# chromatron_v1_0.net
KiCad netlist of a schematic drawn in EAGLE
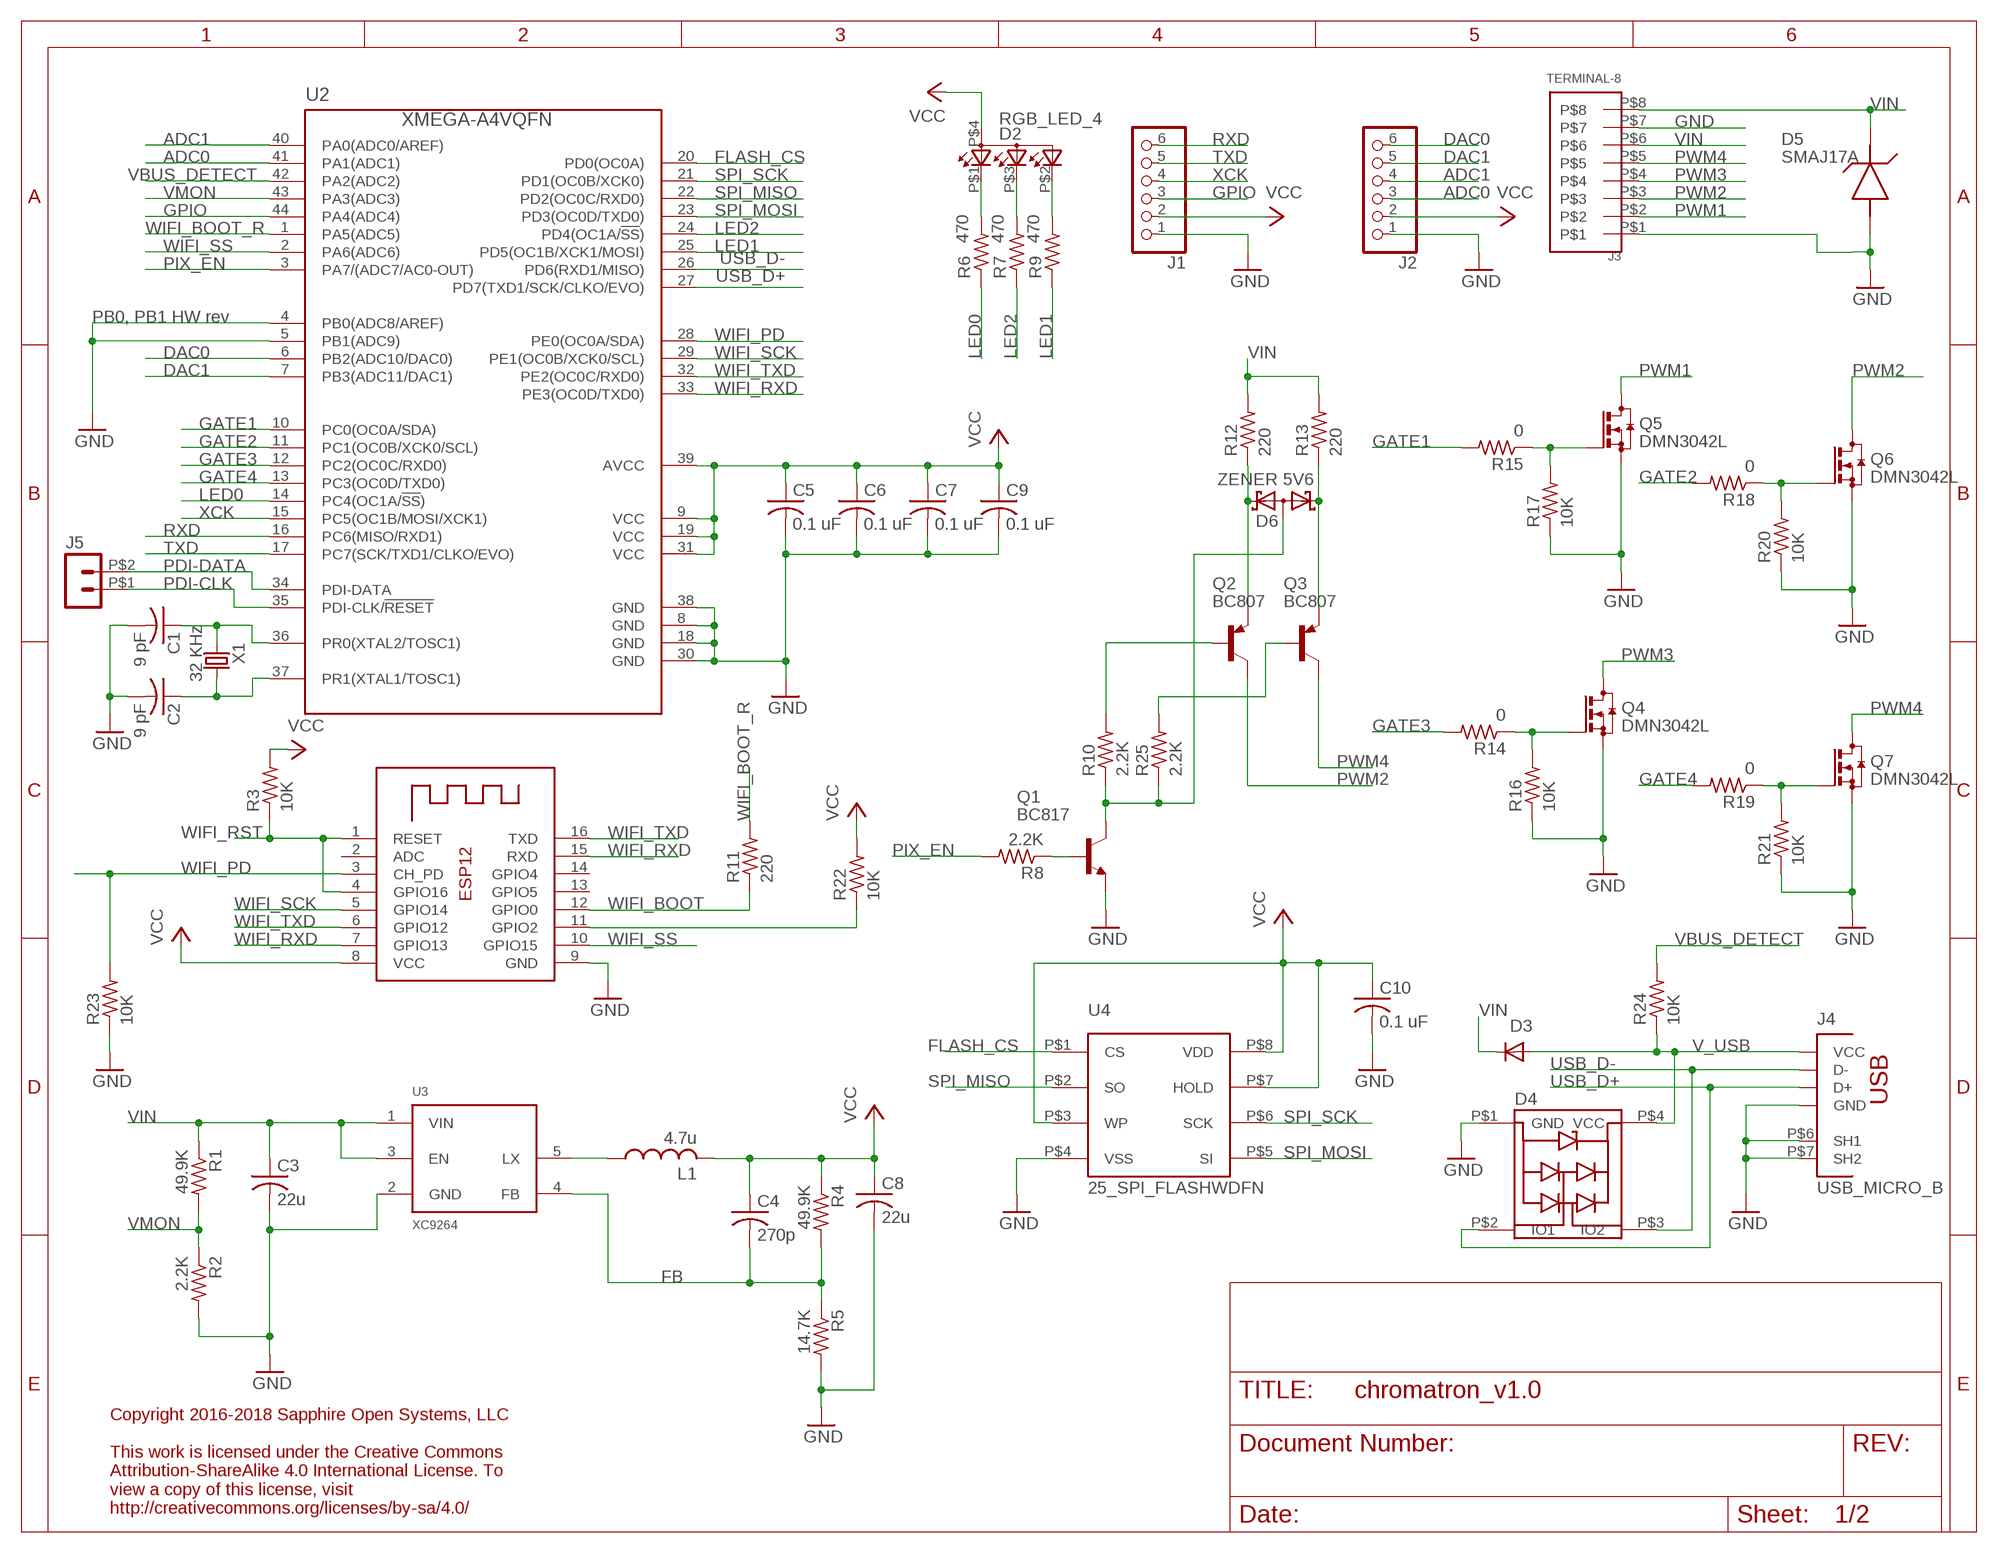
[diagram p0: schematic, sheet 1]
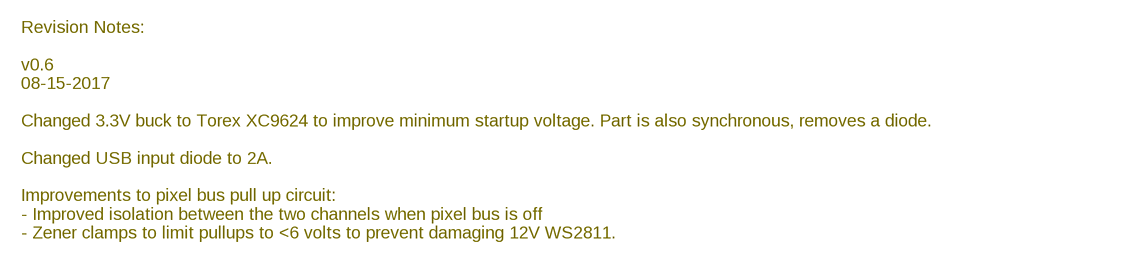
[diagram p1: schematic, sheet 2]

(export (version "E")
  (design (tool "Eeschema 10.0.6"))
  (components
    (comp (ref "C1")
      (value "9 pF")
      (footprint "eagle-import:C0402")
      (libsource (lib "eagle-import") (part "C-USC0402"))
    )
    (comp (ref "C2")
      (value "9 pF")
      (footprint "eagle-import:C0402")
      (libsource (lib "eagle-import") (part "C-USC0402"))
    )
    (comp (ref "C3")
      (value "22u")
      (footprint "eagle-import:C1206")
      (libsource (lib "eagle-import") (part "C-USC1206"))
    )
    (comp (ref "C4")
      (value "270p")
      (footprint "eagle-import:C0402")
      (libsource (lib "eagle-import") (part "C-USC0402"))
    )
    (comp (ref "C5")
      (value "0.1 uF")
      (footprint "eagle-import:C0402")
      (libsource (lib "eagle-import") (part "C-USC0402"))
    )
    (comp (ref "C6")
      (value "0.1 uF")
      (footprint "eagle-import:C0402")
      (libsource (lib "eagle-import") (part "C-USC0402"))
    )
    (comp (ref "C7")
      (value "0.1 uF")
      (footprint "eagle-import:C0402")
      (libsource (lib "eagle-import") (part "C-USC0402"))
    )
    (comp (ref "C8")
      (value "22u")
      (footprint "eagle-import:C1206")
      (libsource (lib "eagle-import") (part "C-USC1206"))
    )
    (comp (ref "C9")
      (value "0.1 uF")
      (footprint "eagle-import:C0402")
      (libsource (lib "eagle-import") (part "C-USC0402"))
    )
    (comp (ref "C10")
      (value "0.1 uF")
      (footprint "eagle-import:C0402")
      (libsource (lib "eagle-import") (part "C-USC0402"))
    )
    (comp (ref "D2")
      (value "RGB_LED_4")
      (footprint "eagle-import:0606-4")
      (libsource (lib "eagle-import") (part "RGB_LED_4"))
    )
    (comp (ref "D3")
      (value "2A")
      (footprint "eagle-import:SOD-123FL")
      (libsource (lib "eagle-import") (part "DIODE_SOD-123FL"))
    )
    (comp (ref "D4")
      (value "PTRTR5V0U2X")
      (footprint "eagle-import:SOT-143B")
      (libsource (lib "eagle-import") (part "PTRTR5V0U2X"))
    )
    (comp (ref "D5")
      (value "SMAJ17A")
      (footprint "eagle-import:SMA")
      (libsource (lib "eagle-import") (part "SMA_TVS"))
    )
    (comp (ref "D6")
      (value "ZENER 5V6")
      (footprint "eagle-import:SOT23")
      (libsource (lib "eagle-import") (part "BAT54A"))
    )
    (comp (ref "J1")
      (value "PINHD-1X6")
      (footprint "eagle-import:1X06")
      (libsource (lib "eagle-import") (part "PINHD-1X6"))
    )
    (comp (ref "J2")
      (value "PINHD-1X6")
      (footprint "eagle-import:1X06")
      (libsource (lib "eagle-import") (part "PINHD-1X6"))
    )
    (comp (ref "J3")
      (value "TERMINAL-8")
      (footprint "eagle-import:TERMINAL-8")
      (libsource (lib "eagle-import") (part "TERMINAL-8"))
    )
    (comp (ref "J4")
      (value "USB_MICRO_B")
      (footprint "eagle-import:USB-MICRO-B")
      (libsource (lib "eagle-import") (part "USB_MICRO_B"))
    )
    (comp (ref "J5")
      (value "PIN_HEADER_1X2")
      (footprint "eagle-import:PIN_HEADER_1X2")
      (libsource (lib "eagle-import") (part "PIN_HEADER_1X2"))
    )
    (comp (ref "L1")
      (value "4.7u")
      (footprint "eagle-import:L2012C")
      (libsource (lib "eagle-import") (part "L-USL2012C"))
    )
    (comp (ref "Q1")
      (value "BC817")
      (footprint "eagle-import:SOT23")
      (libsource (lib "eagle-import") (part "NPN"))
    )
    (comp (ref "Q2")
      (value "BC807")
      (footprint "eagle-import:SOT23")
      (libsource (lib "eagle-import") (part "PNP"))
    )
    (comp (ref "Q3")
      (value "BC807")
      (footprint "eagle-import:SOT23")
      (libsource (lib "eagle-import") (part "PNP"))
    )
    (comp (ref "Q4")
      (value "DMN3042L")
      (footprint "eagle-import:SOT23")
      (libsource (lib "eagle-import") (part "BSS123"))
    )
    (comp (ref "Q5")
      (value "DMN3042L")
      (footprint "eagle-import:SOT23")
      (libsource (lib "eagle-import") (part "BSS123"))
    )
    (comp (ref "Q6")
      (value "DMN3042L")
      (footprint "eagle-import:SOT23")
      (libsource (lib "eagle-import") (part "BSS123"))
    )
    (comp (ref "Q7")
      (value "DMN3042L")
      (footprint "eagle-import:SOT23")
      (libsource (lib "eagle-import") (part "BSS123"))
    )
    (comp (ref "R1")
      (value "49.9K")
      (footprint "eagle-import:R0402")
      (libsource (lib "eagle-import") (part "R-US_R0402"))
    )
    (comp (ref "R2")
      (value "2.2K")
      (footprint "eagle-import:R0402")
      (libsource (lib "eagle-import") (part "R-US_R0402"))
    )
    (comp (ref "R3")
      (value "10K")
      (footprint "eagle-import:R0402")
      (libsource (lib "eagle-import") (part "R-US_R0402"))
    )
    (comp (ref "R4")
      (value "49.9K")
      (footprint "eagle-import:R0402")
      (libsource (lib "eagle-import") (part "R-US_R0402"))
    )
    (comp (ref "R5")
      (value "14.7K")
      (footprint "eagle-import:R0402")
      (libsource (lib "eagle-import") (part "R-US_R0402"))
    )
    (comp (ref "R6")
      (value "470")
      (footprint "eagle-import:R0402")
      (libsource (lib "eagle-import") (part "R-US_R0402"))
    )
    (comp (ref "R7")
      (value "470")
      (footprint "eagle-import:R0402")
      (libsource (lib "eagle-import") (part "R-US_R0402"))
    )
    (comp (ref "R8")
      (value "2.2K")
      (footprint "eagle-import:R0402")
      (libsource (lib "eagle-import") (part "R-US_R0402"))
    )
    (comp (ref "R9")
      (value "470")
      (footprint "eagle-import:R0402")
      (libsource (lib "eagle-import") (part "R-US_R0402"))
    )
    (comp (ref "R10")
      (value "2.2K")
      (footprint "eagle-import:R0402")
      (libsource (lib "eagle-import") (part "R-US_R0402"))
    )
    (comp (ref "R11")
      (value "220")
      (footprint "eagle-import:R0402")
      (libsource (lib "eagle-import") (part "R-US_R0402"))
    )
    (comp (ref "R12")
      (value "220")
      (footprint "eagle-import:R0402")
      (libsource (lib "eagle-import") (part "R-US_R0402"))
    )
    (comp (ref "R13")
      (value "220")
      (footprint "eagle-import:R0402")
      (libsource (lib "eagle-import") (part "R-US_R0402"))
    )
    (comp (ref "R14")
      (value "0")
      (footprint "eagle-import:R0402")
      (libsource (lib "eagle-import") (part "R-US_R0402"))
    )
    (comp (ref "R15")
      (value "0")
      (footprint "eagle-import:R0402")
      (libsource (lib "eagle-import") (part "R-US_R0402"))
    )
    (comp (ref "R16")
      (value "10K")
      (footprint "eagle-import:R0402")
      (libsource (lib "eagle-import") (part "R-US_R0402"))
    )
    (comp (ref "R17")
      (value "10K")
      (footprint "eagle-import:R0402")
      (libsource (lib "eagle-import") (part "R-US_R0402"))
    )
    (comp (ref "R18")
      (value "0")
      (footprint "eagle-import:R0402")
      (libsource (lib "eagle-import") (part "R-US_R0402"))
    )
    (comp (ref "R19")
      (value "0")
      (footprint "eagle-import:R0402")
      (libsource (lib "eagle-import") (part "R-US_R0402"))
    )
    (comp (ref "R20")
      (value "10K")
      (footprint "eagle-import:R0402")
      (libsource (lib "eagle-import") (part "R-US_R0402"))
    )
    (comp (ref "R21")
      (value "10K")
      (footprint "eagle-import:R0402")
      (libsource (lib "eagle-import") (part "R-US_R0402"))
    )
    (comp (ref "R22")
      (value "10K")
      (footprint "eagle-import:R0402")
      (libsource (lib "eagle-import") (part "R-US_R0402"))
    )
    (comp (ref "R23")
      (value "10K")
      (footprint "eagle-import:R0402")
      (libsource (lib "eagle-import") (part "R-US_R0402"))
    )
    (comp (ref "R24")
      (value "10K")
      (footprint "eagle-import:R0402")
      (libsource (lib "eagle-import") (part "R-US_R0402"))
    )
    (comp (ref "R25")
      (value "2.2K")
      (footprint "eagle-import:R0402")
      (libsource (lib "eagle-import") (part "R-US_R0402"))
    )
    (comp (ref "U1")
      (value "ESP-12")
      (footprint "eagle-import:ESP-12")
      (libsource (lib "eagle-import") (part "ESP-12"))
    )
    (comp (ref "U2")
      (value "XMEGA-A4VQFN")
      (footprint "eagle-import:QFN44")
      (libsource (lib "eagle-import") (part "XMEGA-A4VQFN"))
    )
    (comp (ref "U3")
      (value "XC9264")
      (footprint "eagle-import:SOT-25")
      (libsource (lib "eagle-import") (part "XC9264"))
    )
    (comp (ref "U4")
      (value "25_SPI_FLASHWDFN")
      (footprint "eagle-import:WDFN-8")
      (libsource (lib "eagle-import") (part "25_SPI_FLASHWDFN"))
    )
    (comp (ref "X1")
      (value "32 KHz")
      (footprint "eagle-import:XTAL_3.2X1.5")
      (libsource (lib "eagle-import") (part "CRYSTAL_3.2X1.5"))
    )
  )
  (nets
    (net (code "1") (name "ADC0") (class "Default")
      (node (ref "J2") (pin "3") (pinfunction "3_3") (pintype "passive"))
      (node (ref "U2") (pin "41") (pinfunction "PA1(ADC1)_41") (pintype "bidirectional"))
    )
    (net (code "2") (name "ADC1") (class "Default")
      (node (ref "J2") (pin "4") (pinfunction "4_4") (pintype "passive"))
      (node (ref "U2") (pin "40") (pinfunction "PA0(ADC0/AREF)_40") (pintype "bidirectional"))
    )
    (net (code "3") (name "DAC0") (class "Default")
      (node (ref "J2") (pin "6") (pinfunction "6_6") (pintype "passive"))
      (node (ref "U2") (pin "6") (pinfunction "PB2(ADC10/DAC0)_6") (pintype "bidirectional"))
    )
    (net (code "4") (name "DAC1") (class "Default")
      (node (ref "J2") (pin "5") (pinfunction "5_5") (pintype "passive"))
      (node (ref "U2") (pin "7") (pinfunction "PB3(ADC11/DAC1)_7") (pintype "bidirectional"))
    )
    (net (code "5") (name "FB") (class "Default")
      (node (ref "C4") (pin "2") (pinfunction "2_2") (pintype "passive"))
      (node (ref "R4") (pin "2") (pinfunction "2_2") (pintype "passive"))
      (node (ref "R5") (pin "1") (pinfunction "1_1") (pintype "passive"))
      (node (ref "U3") (pin "4") (pinfunction "FB_4") (pintype "bidirectional"))
    )
    (net (code "6") (name "FLASH_CS") (class "Default")
      (node (ref "U2") (pin "20") (pinfunction "PD0(OC0A)_20") (pintype "bidirectional"))
      (node (ref "U4") (pin "P$1") (pinfunction "CS_P$1") (pintype "bidirectional"))
    )
    (net (code "7") (name "GATE1") (class "Default")
      (node (ref "R15") (pin "2") (pinfunction "2_2") (pintype "passive"))
      (node (ref "U2") (pin "10") (pinfunction "PC0(OC0A/SDA)_10") (pintype "bidirectional"))
    )
    (net (code "8") (name "GATE2") (class "Default")
      (node (ref "R18") (pin "2") (pinfunction "2_2") (pintype "passive"))
      (node (ref "U2") (pin "11") (pinfunction "PC1(OC0B/XCK0/SCL)_11") (pintype "bidirectional"))
    )
    (net (code "9") (name "GATE3") (class "Default")
      (node (ref "R14") (pin "2") (pinfunction "2_2") (pintype "passive"))
      (node (ref "U2") (pin "12") (pinfunction "PC2(OC0C/RXD0)_12") (pintype "bidirectional"))
    )
    (net (code "10") (name "GATE4") (class "Default")
      (node (ref "R19") (pin "2") (pinfunction "2_2") (pintype "passive"))
      (node (ref "U2") (pin "13") (pinfunction "PC3(OC0D/TXD0)_13") (pintype "bidirectional"))
    )
    (net (code "11") (name "GND") (class "Default")
      (node (ref "C1") (pin "2") (pinfunction "2_2") (pintype "passive"))
      (node (ref "C10") (pin "2") (pinfunction "2_2") (pintype "passive"))
      (node (ref "C2") (pin "2") (pinfunction "2_2") (pintype "passive"))
      (node (ref "C3") (pin "2") (pinfunction "2_2") (pintype "passive"))
      (node (ref "C5") (pin "2") (pinfunction "2_2") (pintype "passive"))
      (node (ref "C6") (pin "2") (pinfunction "2_2") (pintype "passive"))
      (node (ref "C7") (pin "2") (pinfunction "2_2") (pintype "passive"))
      (node (ref "C8") (pin "2") (pinfunction "2_2") (pintype "passive"))
      (node (ref "C9") (pin "2") (pinfunction "2_2") (pintype "passive"))
      (node (ref "D4") (pin "P$1") (pinfunction "GND_P$1") (pintype "bidirectional"))
      (node (ref "D5") (pin "P$2") (pinfunction "GND_P$2") (pintype "bidirectional"))
      (node (ref "J1") (pin "1") (pinfunction "1_1") (pintype "passive"))
      (node (ref "J2") (pin "1") (pinfunction "1_1") (pintype "passive"))
      (node (ref "J3") (pin "P$1") (pinfunction "P$1_P$1") (pintype "bidirectional"))
      (node (ref "J3") (pin "P$7") (pinfunction "P$7_P$7") (pintype "bidirectional"))
      (node (ref "J4") (pin "P$5") (pinfunction "GND_P$5") (pintype "bidirectional"))
      (node (ref "J4") (pin "P$6") (pinfunction "SH1_P$6") (pintype "bidirectional"))
      (node (ref "J4") (pin "P$7") (pinfunction "SH2_P$7") (pintype "bidirectional"))
      (node (ref "Q1") (pin "2") (pinfunction "E_2") (pintype "passive"))
      (node (ref "Q4") (pin "2") (pinfunction "S_2") (pintype "passive"))
      (node (ref "Q5") (pin "2") (pinfunction "S_2") (pintype "passive"))
      (node (ref "Q6") (pin "2") (pinfunction "S_2") (pintype "passive"))
      (node (ref "Q7") (pin "2") (pinfunction "S_2") (pintype "passive"))
      (node (ref "R16") (pin "1") (pinfunction "1_1") (pintype "passive"))
      (node (ref "R17") (pin "1") (pinfunction "1_1") (pintype "passive"))
      (node (ref "R2") (pin "2") (pinfunction "2_2") (pintype "passive"))
      (node (ref "R20") (pin "1") (pinfunction "1_1") (pintype "passive"))
      (node (ref "R21") (pin "1") (pinfunction "1_1") (pintype "passive"))
      (node (ref "R23") (pin "1") (pinfunction "1_1") (pintype "passive"))
      (node (ref "R5") (pin "2") (pinfunction "2_2") (pintype "passive"))
      (node (ref "U1") (pin "9") (pinfunction "GND_9") (pintype "power_in"))
      (node (ref "U2") (pin "18") (pinfunction "GND_18") (pintype "power_in"))
      (node (ref "U2") (pin "30") (pinfunction "GND_30") (pintype "power_in"))
      (node (ref "U2") (pin "38") (pinfunction "GND_38") (pintype "power_in"))
      (node (ref "U2") (pin "4") (pinfunction "PB0(ADC8/AREF)_4") (pintype "bidirectional"))
      (node (ref "U2") (pin "5") (pinfunction "PB1(ADC9)_5") (pintype "bidirectional"))
      (node (ref "U2") (pin "8") (pinfunction "GND_8") (pintype "power_in"))
      (node (ref "U3") (pin "2") (pinfunction "GND_2") (pintype "bidirectional"))
      (node (ref "U4") (pin "P$4") (pinfunction "VSS_P$4") (pintype "bidirectional"))
    )
    (net (code "12") (name "GPIO") (class "Default")
      (node (ref "J1") (pin "3") (pinfunction "3_3") (pintype "passive"))
      (node (ref "U2") (pin "44") (pinfunction "PA4(ADC4)_44") (pintype "bidirectional"))
    )
    (net (code "13") (name "LED0") (class "Default")
      (node (ref "R6") (pin "1") (pinfunction "1_1") (pintype "passive"))
      (node (ref "U2") (pin "14") (pinfunction "PC4(OC1A/~{SS})_14") (pintype "bidirectional"))
    )
    (net (code "14") (name "LED1") (class "Default")
      (node (ref "R9") (pin "1") (pinfunction "1_1") (pintype "passive"))
      (node (ref "U2") (pin "25") (pinfunction "PD5(OC1B/XCK1/MOSI)_25") (pintype "bidirectional"))
    )
    (net (code "15") (name "LED2") (class "Default")
      (node (ref "R7") (pin "1") (pinfunction "1_1") (pintype "passive"))
      (node (ref "U2") (pin "24") (pinfunction "PD4(OC1A/~{SS})_24") (pintype "bidirectional"))
    )
    (net (code "16") (name "Net-(D2-CBLUE)") (class "Default")
      (node (ref "D2") (pin "P$3") (pinfunction "CBLUE_P$3") (pintype "passive"))
      (node (ref "R7") (pin "2") (pinfunction "2_2") (pintype "passive"))
    )
    (net (code "17") (name "Net-(D2-CGREEN)") (class "Default")
      (node (ref "D2") (pin "P$2") (pinfunction "CGREEN_P$2") (pintype "passive"))
      (node (ref "R9") (pin "2") (pinfunction "2_2") (pintype "passive"))
    )
    (net (code "18") (name "Net-(D2-CRED)") (class "Default")
      (node (ref "D2") (pin "P$1") (pinfunction "CRED_P$1") (pintype "passive"))
      (node (ref "R6") (pin "2") (pinfunction "2_2") (pintype "passive"))
    )
    (net (code "19") (name "Net-(D6-AA)") (class "Default")
      (node (ref "D6") (pin "3") (pinfunction "AA_3") (pintype "passive"))
      (node (ref "Q1") (pin "3") (pinfunction "C_3") (pintype "passive"))
      (node (ref "R10") (pin "1") (pinfunction "1_1") (pintype "passive"))
      (node (ref "R25") (pin "1") (pinfunction "1_1") (pintype "passive"))
    )
    (net (code "20") (name "Net-(D6-K1)") (class "Default")
      (node (ref "D6") (pin "1") (pinfunction "K1_1") (pintype "passive"))
      (node (ref "Q3") (pin "2") (pinfunction "E_2") (pintype "passive"))
      (node (ref "R13") (pin "1") (pinfunction "1_1") (pintype "passive"))
    )
    (net (code "21") (name "Net-(D6-K2)") (class "Default")
      (node (ref "D6") (pin "2") (pinfunction "K2_2") (pintype "passive"))
      (node (ref "Q2") (pin "2") (pinfunction "E_2") (pintype "passive"))
      (node (ref "R12") (pin "1") (pinfunction "1_1") (pintype "passive"))
    )
    (net (code "22") (name "Net-(Q1-B)") (class "Default")
      (node (ref "Q1") (pin "1") (pinfunction "B_1") (pintype "passive"))
      (node (ref "R8") (pin "1") (pinfunction "1_1") (pintype "passive"))
    )
    (net (code "23") (name "Net-(Q2-B)") (class "Default")
      (node (ref "Q2") (pin "1") (pinfunction "B_1") (pintype "passive"))
      (node (ref "R10") (pin "2") (pinfunction "2_2") (pintype "passive"))
    )
    (net (code "24") (name "Net-(Q3-B)") (class "Default")
      (node (ref "Q3") (pin "1") (pinfunction "B_1") (pintype "passive"))
      (node (ref "R25") (pin "2") (pinfunction "2_2") (pintype "passive"))
    )
    (net (code "25") (name "Net-(Q4-G)") (class "Default")
      (node (ref "Q4") (pin "1") (pinfunction "G_1") (pintype "passive"))
      (node (ref "R14") (pin "1") (pinfunction "1_1") (pintype "passive"))
      (node (ref "R16") (pin "2") (pinfunction "2_2") (pintype "passive"))
    )
    (net (code "26") (name "Net-(Q5-G)") (class "Default")
      (node (ref "Q5") (pin "1") (pinfunction "G_1") (pintype "passive"))
      (node (ref "R15") (pin "1") (pinfunction "1_1") (pintype "passive"))
      (node (ref "R17") (pin "2") (pinfunction "2_2") (pintype "passive"))
    )
    (net (code "27") (name "Net-(Q6-G)") (class "Default")
      (node (ref "Q6") (pin "1") (pinfunction "G_1") (pintype "passive"))
      (node (ref "R18") (pin "1") (pinfunction "1_1") (pintype "passive"))
      (node (ref "R20") (pin "2") (pinfunction "2_2") (pintype "passive"))
    )
    (net (code "28") (name "Net-(Q7-G)") (class "Default")
      (node (ref "Q7") (pin "1") (pinfunction "G_1") (pintype "passive"))
      (node (ref "R19") (pin "1") (pinfunction "1_1") (pintype "passive"))
      (node (ref "R21") (pin "2") (pinfunction "2_2") (pintype "passive"))
    )
    (net (code "29") (name "Net-(U1-GPIO2)") (class "Default")
      (node (ref "R22") (pin "1") (pinfunction "1_1") (pintype "passive"))
      (node (ref "U1") (pin "11") (pinfunction "GPIO2_11") (pintype "bidirectional"))
    )
    (net (code "30") (name "Net-(U2-PR0(XTAL2{slash}TOSC1))") (class "Default")
      (node (ref "C1") (pin "1") (pinfunction "1_1") (pintype "passive"))
      (node (ref "U2") (pin "36") (pinfunction "PR0(XTAL2/TOSC1)_36") (pintype "bidirectional"))
      (node (ref "X1") (pin "P$1") (pinfunction "1_P$1") (pintype "passive"))
    )
    (net (code "31") (name "Net-(U2-PR1(XTAL1{slash}TOSC1))") (class "Default")
      (node (ref "C2") (pin "1") (pinfunction "1_1") (pintype "passive"))
      (node (ref "U2") (pin "37") (pinfunction "PR1(XTAL1/TOSC1)_37") (pintype "bidirectional"))
      (node (ref "X1") (pin "P$2") (pinfunction "2_P$2") (pintype "passive"))
    )
    (net (code "32") (name "Net-(U3-LX)") (class "Default")
      (node (ref "L1") (pin "1") (pinfunction "1_1") (pintype "passive"))
      (node (ref "U3") (pin "5") (pinfunction "LX_5") (pintype "bidirectional"))
    )
    (net (code "33") (name "PDI-CLK") (class "Default")
      (node (ref "J5") (pin "P$1") (pinfunction "1_P$1") (pintype "passive"))
      (node (ref "U2") (pin "35") (pinfunction "PDI-CLK/~{RESET}_35") (pintype "input"))
    )
    (net (code "34") (name "PDI-DATA") (class "Default")
      (node (ref "J5") (pin "P$2") (pinfunction "2_P$2") (pintype "passive"))
      (node (ref "U2") (pin "34") (pinfunction "PDI-DATA_34") (pintype "bidirectional"))
    )
    (net (code "35") (name "PIX_EN") (class "Default")
      (node (ref "R8") (pin "2") (pinfunction "2_2") (pintype "passive"))
      (node (ref "U2") (pin "3") (pinfunction "PA7/(ADC7/AC0-OUT)_3") (pintype "bidirectional"))
    )
    (net (code "36") (name "PWM1") (class "Default")
      (node (ref "J3") (pin "P$2") (pinfunction "P$2_P$2") (pintype "bidirectional"))
      (node (ref "Q5") (pin "3") (pinfunction "D_3") (pintype "passive"))
    )
    (net (code "37") (name "PWM2") (class "Default")
      (node (ref "J3") (pin "P$3") (pinfunction "P$3_P$3") (pintype "bidirectional"))
      (node (ref "Q2") (pin "3") (pinfunction "C_3") (pintype "passive"))
      (node (ref "Q6") (pin "3") (pinfunction "D_3") (pintype "passive"))
    )
    (net (code "38") (name "PWM3") (class "Default")
      (node (ref "J3") (pin "P$4") (pinfunction "P$4_P$4") (pintype "bidirectional"))
      (node (ref "Q4") (pin "3") (pinfunction "D_3") (pintype "passive"))
    )
    (net (code "39") (name "PWM4") (class "Default")
      (node (ref "J3") (pin "P$5") (pinfunction "P$5_P$5") (pintype "bidirectional"))
      (node (ref "Q3") (pin "3") (pinfunction "C_3") (pintype "passive"))
      (node (ref "Q7") (pin "3") (pinfunction "D_3") (pintype "passive"))
    )
    (net (code "40") (name "RXD") (class "Default")
      (node (ref "J1") (pin "6") (pinfunction "6_6") (pintype "passive"))
      (node (ref "U2") (pin "16") (pinfunction "PC6(MISO/RXD1)_16") (pintype "bidirectional"))
    )
    (net (code "41") (name "SPI_MISO") (class "Default")
      (node (ref "U2") (pin "22") (pinfunction "PD2(OC0C/RXD0)_22") (pintype "bidirectional"))
      (node (ref "U4") (pin "P$2") (pinfunction "SO_P$2") (pintype "bidirectional"))
    )
    (net (code "42") (name "SPI_MOSI") (class "Default")
      (node (ref "U2") (pin "23") (pinfunction "PD3(OC0D/TXD0)_23") (pintype "bidirectional"))
      (node (ref "U4") (pin "P$5") (pinfunction "SI_P$5") (pintype "bidirectional"))
    )
    (net (code "43") (name "SPI_SCK") (class "Default")
      (node (ref "U2") (pin "21") (pinfunction "PD1(OC0B/XCK0)_21") (pintype "bidirectional"))
      (node (ref "U4") (pin "P$6") (pinfunction "SCK_P$6") (pintype "bidirectional"))
    )
    (net (code "44") (name "TXD") (class "Default")
      (node (ref "J1") (pin "5") (pinfunction "5_5") (pintype "passive"))
      (node (ref "U2") (pin "17") (pinfunction "PC7(SCK/TXD1/CLKO/EVO)_17") (pintype "bidirectional"))
    )
    (net (code "45") (name "USB_D+") (class "Default")
      (node (ref "D4") (pin "P$2") (pinfunction "IO1_P$2") (pintype "bidirectional"))
      (node (ref "J4") (pin "P$3") (pinfunction "D+_P$3") (pintype "bidirectional"))
      (node (ref "U2") (pin "27") (pinfunction "PD7(TXD1/SCK/CLKO/EVO)_27") (pintype "bidirectional"))
    )
    (net (code "46") (name "USB_D-") (class "Default")
      (node (ref "D4") (pin "P$3") (pinfunction "IO2_P$3") (pintype "bidirectional"))
      (node (ref "J4") (pin "P$2") (pinfunction "D-_P$2") (pintype "bidirectional"))
      (node (ref "U2") (pin "26") (pinfunction "PD6(RXD1/MISO)_26") (pintype "bidirectional"))
    )
    (net (code "47") (name "VBUS_DETECT") (class "Default")
      (node (ref "R24") (pin "2") (pinfunction "2_2") (pintype "passive"))
      (node (ref "U2") (pin "42") (pinfunction "PA2(ADC2)_42") (pintype "bidirectional"))
    )
    (net (code "48") (name "VCC") (class "Default")
      (node (ref "C10") (pin "1") (pinfunction "1_1") (pintype "passive"))
      (node (ref "C4") (pin "1") (pinfunction "1_1") (pintype "passive"))
      (node (ref "C5") (pin "1") (pinfunction "1_1") (pintype "passive"))
      (node (ref "C6") (pin "1") (pinfunction "1_1") (pintype "passive"))
      (node (ref "C7") (pin "1") (pinfunction "1_1") (pintype "passive"))
      (node (ref "C8") (pin "1") (pinfunction "1_1") (pintype "passive"))
      (node (ref "C9") (pin "1") (pinfunction "1_1") (pintype "passive"))
      (node (ref "D2") (pin "P$4") (pinfunction "A2_P$4") (pintype "passive"))
      (node (ref "J1") (pin "2") (pinfunction "2_2") (pintype "passive"))
      (node (ref "J2") (pin "2") (pinfunction "2_2") (pintype "passive"))
      (node (ref "L1") (pin "2") (pinfunction "2_2") (pintype "passive"))
      (node (ref "R22") (pin "2") (pinfunction "2_2") (pintype "passive"))
      (node (ref "R3") (pin "2") (pinfunction "2_2") (pintype "passive"))
      (node (ref "R4") (pin "1") (pinfunction "1_1") (pintype "passive"))
      (node (ref "U1") (pin "8") (pinfunction "VCC_8") (pintype "power_in"))
      (node (ref "U2") (pin "19") (pinfunction "VCC_19") (pintype "power_in"))
      (node (ref "U2") (pin "31") (pinfunction "VCC_31") (pintype "power_in"))
      (node (ref "U2") (pin "39") (pinfunction "AVCC_39") (pintype "power_in"))
      (node (ref "U2") (pin "9") (pinfunction "VCC_9") (pintype "power_in"))
      (node (ref "U4") (pin "P$3") (pinfunction "WP_P$3") (pintype "bidirectional"))
      (node (ref "U4") (pin "P$7") (pinfunction "HOLD_P$7") (pintype "bidirectional"))
      (node (ref "U4") (pin "P$8") (pinfunction "VDD_P$8") (pintype "bidirectional"))
    )
    (net (code "49") (name "VIN") (class "Default")
      (node (ref "C3") (pin "1") (pinfunction "1_1") (pintype "passive"))
      (node (ref "D3") (pin "C") (pinfunction "C_C") (pintype "passive"))
      (node (ref "D5") (pin "P$1") (pinfunction "LINE_P$1") (pintype "bidirectional"))
      (node (ref "J3") (pin "P$6") (pinfunction "P$6_P$6") (pintype "bidirectional"))
      (node (ref "J3") (pin "P$8") (pinfunction "P$8_P$8") (pintype "bidirectional"))
      (node (ref "R1") (pin "1") (pinfunction "1_1") (pintype "passive"))
      (node (ref "R12") (pin "2") (pinfunction "2_2") (pintype "passive"))
      (node (ref "R13") (pin "2") (pinfunction "2_2") (pintype "passive"))
      (node (ref "U3") (pin "1") (pinfunction "VIN_1") (pintype "bidirectional"))
      (node (ref "U3") (pin "3") (pinfunction "EN_3") (pintype "bidirectional"))
    )
    (net (code "50") (name "VMON") (class "Default")
      (node (ref "R1") (pin "2") (pinfunction "2_2") (pintype "passive"))
      (node (ref "R2") (pin "1") (pinfunction "1_1") (pintype "passive"))
      (node (ref "U2") (pin "43") (pinfunction "PA3(ADC3)_43") (pintype "bidirectional"))
    )
    (net (code "51") (name "V_USB") (class "Default")
      (node (ref "D3") (pin "A") (pinfunction "A_A") (pintype "passive"))
      (node (ref "D4") (pin "P$4") (pinfunction "VCC_P$4") (pintype "bidirectional"))
      (node (ref "J4") (pin "P$1") (pinfunction "VCC_P$1") (pintype "bidirectional"))
      (node (ref "R24") (pin "1") (pinfunction "1_1") (pintype "passive"))
    )
    (net (code "52") (name "WIFI_BOOT") (class "Default")
      (node (ref "R11") (pin "1") (pinfunction "1_1") (pintype "passive"))
      (node (ref "U1") (pin "12") (pinfunction "GPIO0_12") (pintype "bidirectional"))
    )
    (net (code "53") (name "WIFI_BOOT_R") (class "Default")
      (node (ref "R11") (pin "2") (pinfunction "2_2") (pintype "passive"))
      (node (ref "U2") (pin "1") (pinfunction "PA5(ADC5)_1") (pintype "bidirectional"))
    )
    (net (code "54") (name "WIFI_PD") (class "Default")
      (node (ref "R23") (pin "2") (pinfunction "2_2") (pintype "passive"))
      (node (ref "U1") (pin "3") (pinfunction "CH_PD_3") (pintype "input"))
      (node (ref "U2") (pin "28") (pinfunction "PE0(OC0A/SDA)_28") (pintype "bidirectional"))
    )
    (net (code "55") (name "WIFI_RST") (class "Default")
      (node (ref "R3") (pin "1") (pinfunction "1_1") (pintype "passive"))
      (node (ref "U1") (pin "1") (pinfunction "RESET_1") (pintype "input"))
      (node (ref "U1") (pin "4") (pinfunction "GPIO16_4") (pintype "bidirectional"))
    )
    (net (code "56") (name "WIFI_RXD") (class "Default")
      (node (ref "U1") (pin "15") (pinfunction "RXD_15") (pintype "input"))
      (node (ref "U1") (pin "7") (pinfunction "GPIO13_7") (pintype "bidirectional"))
      (node (ref "U2") (pin "33") (pinfunction "PE3(OC0D/TXD0)_33") (pintype "bidirectional"))
    )
    (net (code "57") (name "WIFI_SCK") (class "Default")
      (node (ref "U1") (pin "5") (pinfunction "GPIO14_5") (pintype "bidirectional"))
      (node (ref "U2") (pin "29") (pinfunction "PE1(OC0B/XCK0/SCL)_29") (pintype "bidirectional"))
    )
    (net (code "58") (name "WIFI_SS") (class "Default")
      (node (ref "U1") (pin "10") (pinfunction "GPIO15_10") (pintype "bidirectional"))
      (node (ref "U2") (pin "2") (pinfunction "PA6(ADC6)_2") (pintype "bidirectional"))
    )
    (net (code "59") (name "WIFI_TXD") (class "Default")
      (node (ref "U1") (pin "16") (pinfunction "TXD_16") (pintype "output"))
      (node (ref "U1") (pin "6") (pinfunction "GPIO12_6") (pintype "bidirectional"))
      (node (ref "U2") (pin "32") (pinfunction "PE2(OC0C/RXD0)_32") (pintype "bidirectional"))
    )
    (net (code "60") (name "XCK") (class "Default")
      (node (ref "J1") (pin "4") (pinfunction "4_4") (pintype "passive"))
      (node (ref "U2") (pin "15") (pinfunction "PC5(OC1B/MOSI/XCK1)_15") (pintype "bidirectional"))
    )
    (net (code "61") (name "unconnected-(U1-ADC-Pad2)") (class "Default")
      (node (ref "U1") (pin "2") (pinfunction "ADC_2") (pintype "passive"))
    )
    (net (code "62") (name "unconnected-(U1-GPIO4-Pad14)") (class "Default")
      (node (ref "U1") (pin "14") (pinfunction "GPIO4_14") (pintype "bidirectional"))
    )
    (net (code "63") (name "unconnected-(U1-GPIO5-Pad13)") (class "Default")
      (node (ref "U1") (pin "13") (pinfunction "GPIO5_13") (pintype "bidirectional"))
    )
  )
)
